# Spark.net
KiCad netlist of a schematic drawn in EAGLE
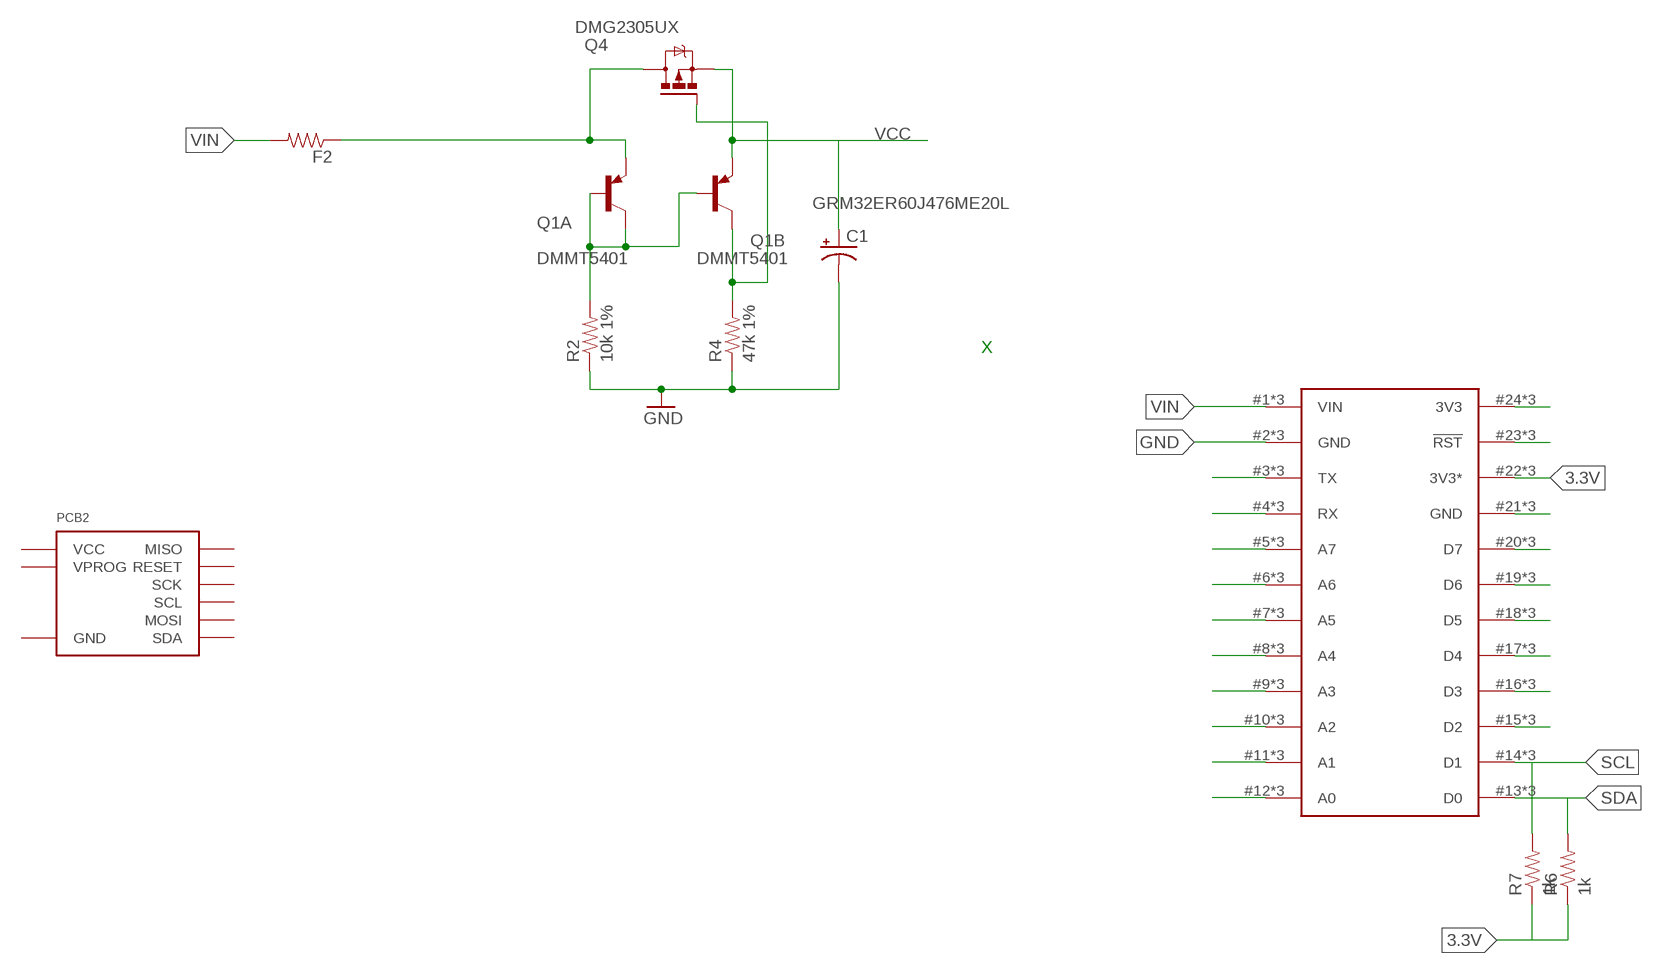
[diagram p0: schematic, sheet 1]

(export (version "E")
  (design (tool "Eeschema 10.0.6"))
  (components
    (comp (ref "C1")
      (value "CAP_POLC")
      (footprint "eagle-import:PANASONIC_C")
      (libsource (lib "eagle-import") (part "CAP_POLC"))
    )
    (comp (ref "F2")
      (value "RESISTOR0805-RES")
      (footprint "eagle-import:0805")
      (libsource (lib "eagle-import") (part "RESISTOR0805-RES"))
    )
    (comp (ref "PCB2")
      (value "EXCLUDE")
      (footprint "eagle-import:DEVICE-PCB")
      (libsource (lib "eagle-import") (part "DEVICE-PCB"))
    )
    (comp (ref "Q1")
      (value "DMMT5401")
      (footprint "eagle-import:SOT-26")
      (libsource (lib "eagle-import") (part "TRANSISTOR-DUAL-PNP"))
    )
    (comp (ref "Q4")
      (value "DMG2305UX")
      (footprint "eagle-import:MICRO3")
      (libsource (lib "eagle-import") (part "IRLML5203"))
    )
    (comp (ref "R2")
      (value "10k 1%")
      (footprint "eagle-import:0805")
      (libsource (lib "eagle-import") (part "RESISTOR0805-RES"))
    )
    (comp (ref "R4")
      (value "47k 1%")
      (footprint "eagle-import:0805")
      (libsource (lib "eagle-import") (part "RESISTOR0805-RES"))
    )
    (comp (ref "R6")
      (value "1k")
      (footprint "eagle-import:0805")
      (libsource (lib "eagle-import") (part "RESISTOR0805-RES"))
    )
    (comp (ref "R7")
      (value "1k")
      (footprint "eagle-import:0805")
      (libsource (lib "eagle-import") (part "RESISTOR0805-RES"))
    )
    (comp (ref "U$1")
      (value "SPARK_CORE")
      (footprint "eagle-import:SPARK_CORE_STACKABLE")
      (libsource (lib "eagle-import") (part "SPARK_CORE"))
    )
  )
  (nets
    (net (code "1") (name "/VCC") (class "Default")
      (node (ref "C1") (pin "+") (pinfunction "+_+") (pintype "passive"))
      (node (ref "Q1") (pin "5") (pinfunction "E_5") (pintype "passive"))
      (node (ref "Q4") (pin "2") (pinfunction "S_2") (pintype "passive"))
    )
    (net (code "2") (name "3.3V") (class "Default")
      (node (ref "R6") (pin "1") (pinfunction "1_1") (pintype "passive"))
      (node (ref "R7") (pin "1") (pinfunction "1_1") (pintype "passive"))
      (node (ref "U$1") (pin "#22") (pinfunction "3V3*_#22") (pintype "power_in"))
      (node (ref "U$1") (pin "22") (pinfunction "3V3*_22") (pintype "power_in"))
      (node (ref "U$1") (pin "@22") (pinfunction "3V3*_@22") (pintype "power_in"))
    )
    (net (code "3") (name "GND") (class "Default")
      (node (ref "C1") (pin "-") (pinfunction "-_-") (pintype "passive"))
      (node (ref "R2") (pin "1") (pinfunction "1_1") (pintype "passive"))
      (node (ref "R4") (pin "1") (pinfunction "1_1") (pintype "passive"))
      (node (ref "U$1") (pin "#2") (pinfunction "GND_#2") (pintype "power_in"))
      (node (ref "U$1") (pin "2") (pinfunction "GND_2") (pintype "power_in"))
      (node (ref "U$1") (pin "@2") (pinfunction "GND_@2") (pintype "power_in"))
    )
    (net (code "4") (name "Net-(Q1A-B)") (class "Default")
      (node (ref "Q1") (pin "1") (pinfunction "C_1") (pintype "passive"))
      (node (ref "Q1") (pin "2") (pinfunction "B_2") (pintype "passive"))
      (node (ref "Q1") (pin "3") (pinfunction "B_3") (pintype "passive"))
      (node (ref "R2") (pin "2") (pinfunction "2_2") (pintype "passive"))
    )
    (net (code "5") (name "Net-(Q1A-E)") (class "Default")
      (node (ref "F2") (pin "1") (pinfunction "1_1") (pintype "passive"))
      (node (ref "Q1") (pin "6") (pinfunction "E_6") (pintype "passive"))
      (node (ref "Q4") (pin "3") (pinfunction "D_3") (pintype "passive"))
    )
    (net (code "6") (name "Net-(Q1B-C)") (class "Default")
      (node (ref "Q1") (pin "4") (pinfunction "C_4") (pintype "passive"))
      (node (ref "Q4") (pin "1") (pinfunction "G_1") (pintype "passive"))
      (node (ref "R4") (pin "2") (pinfunction "2_2") (pintype "passive"))
    )
    (net (code "7") (name "Net-(U$1-3V3-Pad#24)") (class "Default")
      (node (ref "U$1") (pin "#24") (pinfunction "3V3_#24") (pintype "power_in"))
      (node (ref "U$1") (pin "24") (pinfunction "3V3_24") (pintype "power_in"))
      (node (ref "U$1") (pin "@24") (pinfunction "3V3_@24") (pintype "power_in"))
    )
    (net (code "8") (name "Net-(U$1-A0-Pad#12)") (class "Default")
      (node (ref "U$1") (pin "#12") (pinfunction "A0_#12") (pintype "bidirectional"))
      (node (ref "U$1") (pin "12") (pinfunction "A0_12") (pintype "bidirectional"))
      (node (ref "U$1") (pin "@12") (pinfunction "A0_@12") (pintype "bidirectional"))
    )
    (net (code "9") (name "Net-(U$1-A1-Pad#11)") (class "Default")
      (node (ref "U$1") (pin "#11") (pinfunction "A1_#11") (pintype "bidirectional"))
      (node (ref "U$1") (pin "11") (pinfunction "A1_11") (pintype "bidirectional"))
      (node (ref "U$1") (pin "@11") (pinfunction "A1_@11") (pintype "bidirectional"))
    )
    (net (code "10") (name "Net-(U$1-A2-Pad#10)") (class "Default")
      (node (ref "U$1") (pin "#10") (pinfunction "A2_#10") (pintype "bidirectional"))
      (node (ref "U$1") (pin "10") (pinfunction "A2_10") (pintype "bidirectional"))
      (node (ref "U$1") (pin "@10") (pinfunction "A2_@10") (pintype "bidirectional"))
    )
    (net (code "11") (name "Net-(U$1-A3-Pad#9)") (class "Default")
      (node (ref "U$1") (pin "#9") (pinfunction "A3_#9") (pintype "bidirectional"))
      (node (ref "U$1") (pin "9") (pinfunction "A3_9") (pintype "bidirectional"))
      (node (ref "U$1") (pin "@9") (pinfunction "A3_@9") (pintype "bidirectional"))
    )
    (net (code "12") (name "Net-(U$1-A4-Pad#8)") (class "Default")
      (node (ref "U$1") (pin "#8") (pinfunction "A4_#8") (pintype "bidirectional"))
      (node (ref "U$1") (pin "8") (pinfunction "A4_8") (pintype "bidirectional"))
      (node (ref "U$1") (pin "@8") (pinfunction "A4_@8") (pintype "bidirectional"))
    )
    (net (code "13") (name "Net-(U$1-A5-Pad#7)") (class "Default")
      (node (ref "U$1") (pin "#7") (pinfunction "A5_#7") (pintype "bidirectional"))
      (node (ref "U$1") (pin "7") (pinfunction "A5_7") (pintype "bidirectional"))
      (node (ref "U$1") (pin "@7") (pinfunction "A5_@7") (pintype "bidirectional"))
    )
    (net (code "14") (name "Net-(U$1-A6-Pad#6)") (class "Default")
      (node (ref "U$1") (pin "#6") (pinfunction "A6_#6") (pintype "bidirectional"))
      (node (ref "U$1") (pin "6") (pinfunction "A6_6") (pintype "bidirectional"))
      (node (ref "U$1") (pin "@6") (pinfunction "A6_@6") (pintype "bidirectional"))
    )
    (net (code "15") (name "Net-(U$1-A7-Pad#5)") (class "Default")
      (node (ref "U$1") (pin "#5") (pinfunction "A7_#5") (pintype "bidirectional"))
      (node (ref "U$1") (pin "5") (pinfunction "A7_5") (pintype "bidirectional"))
      (node (ref "U$1") (pin "@5") (pinfunction "A7_@5") (pintype "bidirectional"))
    )
    (net (code "16") (name "Net-(U$1-D2-Pad#15)") (class "Default")
      (node (ref "U$1") (pin "#15") (pinfunction "D2_#15") (pintype "bidirectional"))
      (node (ref "U$1") (pin "15") (pinfunction "D2_15") (pintype "bidirectional"))
      (node (ref "U$1") (pin "@15") (pinfunction "D2_@15") (pintype "bidirectional"))
    )
    (net (code "17") (name "Net-(U$1-D3-Pad#16)") (class "Default")
      (node (ref "U$1") (pin "#16") (pinfunction "D3_#16") (pintype "bidirectional"))
      (node (ref "U$1") (pin "16") (pinfunction "D3_16") (pintype "bidirectional"))
      (node (ref "U$1") (pin "@16") (pinfunction "D3_@16") (pintype "bidirectional"))
    )
    (net (code "18") (name "Net-(U$1-D4-Pad#17)") (class "Default")
      (node (ref "U$1") (pin "#17") (pinfunction "D4_#17") (pintype "bidirectional"))
      (node (ref "U$1") (pin "17") (pinfunction "D4_17") (pintype "bidirectional"))
      (node (ref "U$1") (pin "@17") (pinfunction "D4_@17") (pintype "bidirectional"))
    )
    (net (code "19") (name "Net-(U$1-D5-Pad#18)") (class "Default")
      (node (ref "U$1") (pin "#18") (pinfunction "D5_#18") (pintype "bidirectional"))
      (node (ref "U$1") (pin "18") (pinfunction "D5_18") (pintype "bidirectional"))
      (node (ref "U$1") (pin "@18") (pinfunction "D5_@18") (pintype "bidirectional"))
    )
    (net (code "20") (name "Net-(U$1-D6-Pad#19)") (class "Default")
      (node (ref "U$1") (pin "#19") (pinfunction "D6_#19") (pintype "bidirectional"))
      (node (ref "U$1") (pin "19") (pinfunction "D6_19") (pintype "bidirectional"))
      (node (ref "U$1") (pin "@19") (pinfunction "D6_@19") (pintype "bidirectional"))
    )
    (net (code "21") (name "Net-(U$1-D7-Pad#20)") (class "Default")
      (node (ref "U$1") (pin "#20") (pinfunction "D7_#20") (pintype "bidirectional"))
      (node (ref "U$1") (pin "20") (pinfunction "D7_20") (pintype "bidirectional"))
      (node (ref "U$1") (pin "@20") (pinfunction "D7_@20") (pintype "bidirectional"))
    )
    (net (code "22") (name "Net-(U$1-GND-Pad#21)") (class "Default")
      (node (ref "U$1") (pin "#21") (pinfunction "GND_#21") (pintype "power_in"))
      (node (ref "U$1") (pin "21") (pinfunction "GND_21") (pintype "power_in"))
      (node (ref "U$1") (pin "@21") (pinfunction "GND_@21") (pintype "power_in"))
    )
    (net (code "23") (name "Net-(U$1-RX-Pad#4)") (class "Default")
      (node (ref "U$1") (pin "#4") (pinfunction "RX_#4") (pintype "bidirectional"))
      (node (ref "U$1") (pin "4") (pinfunction "RX_4") (pintype "bidirectional"))
      (node (ref "U$1") (pin "@4") (pinfunction "RX_@4") (pintype "bidirectional"))
    )
    (net (code "24") (name "Net-(U$1-TX-Pad#3)") (class "Default")
      (node (ref "U$1") (pin "#3") (pinfunction "TX_#3") (pintype "bidirectional"))
      (node (ref "U$1") (pin "3") (pinfunction "TX_3") (pintype "bidirectional"))
      (node (ref "U$1") (pin "@3") (pinfunction "TX_@3") (pintype "bidirectional"))
    )
    (net (code "25") (name "Net-(U$1-~{RST}-Pad#23)") (class "Default")
      (node (ref "U$1") (pin "#23") (pinfunction "~{RST}_#23") (pintype "bidirectional"))
      (node (ref "U$1") (pin "23") (pinfunction "~{RST}_23") (pintype "bidirectional"))
      (node (ref "U$1") (pin "@23") (pinfunction "~{RST}_@23") (pintype "bidirectional"))
    )
    (net (code "26") (name "SCL") (class "Default")
      (node (ref "R7") (pin "2") (pinfunction "2_2") (pintype "passive"))
      (node (ref "U$1") (pin "#14") (pinfunction "D1_#14") (pintype "bidirectional"))
      (node (ref "U$1") (pin "14") (pinfunction "D1_14") (pintype "bidirectional"))
      (node (ref "U$1") (pin "@14") (pinfunction "D1_@14") (pintype "bidirectional"))
    )
    (net (code "27") (name "SDA") (class "Default")
      (node (ref "R6") (pin "2") (pinfunction "2_2") (pintype "passive"))
      (node (ref "U$1") (pin "#13") (pinfunction "D0_#13") (pintype "bidirectional"))
      (node (ref "U$1") (pin "13") (pinfunction "D0_13") (pintype "bidirectional"))
      (node (ref "U$1") (pin "@13") (pinfunction "D0_@13") (pintype "bidirectional"))
    )
    (net (code "28") (name "VIN") (class "Default")
      (node (ref "F2") (pin "2") (pinfunction "2_2") (pintype "passive"))
      (node (ref "U$1") (pin "#1") (pinfunction "VIN_#1") (pintype "power_in"))
      (node (ref "U$1") (pin "1") (pinfunction "VIN_1") (pintype "power_in"))
      (node (ref "U$1") (pin "@1") (pinfunction "VIN_@1") (pintype "power_in"))
    )
    (net (code "29") (name "unconnected-(PCB2-GND-PadBUS0)") (class "Default")
      (node (ref "PCB2") (pin "BUS0") (pinfunction "GND_BUS0") (pintype "bidirectional"))
    )
    (net (code "30") (name "unconnected-(PCB2-MISO-PadPROG3)") (class "Default")
      (node (ref "PCB2") (pin "PROG3") (pinfunction "MISO_PROG3") (pintype "bidirectional"))
    )
    (net (code "31") (name "unconnected-(PCB2-MOSI-PadPROG4)") (class "Default")
      (node (ref "PCB2") (pin "PROG4") (pinfunction "MOSI_PROG4") (pintype "bidirectional"))
    )
    (net (code "32") (name "unconnected-(PCB2-RESET-PadPROG1)") (class "Default")
      (node (ref "PCB2") (pin "PROG1") (pinfunction "RESET_PROG1") (pintype "bidirectional"))
    )
    (net (code "33") (name "unconnected-(PCB2-SCK-PadPROG2)") (class "Default")
      (node (ref "PCB2") (pin "PROG2") (pinfunction "SCK_PROG2") (pintype "bidirectional"))
    )
    (net (code "34") (name "unconnected-(PCB2-SCL-PadBUS3)") (class "Default")
      (node (ref "PCB2") (pin "BUS3") (pinfunction "SCL_BUS3") (pintype "bidirectional"))
    )
    (net (code "35") (name "unconnected-(PCB2-SDA-PadBUS1)") (class "Default")
      (node (ref "PCB2") (pin "BUS1") (pinfunction "SDA_BUS1") (pintype "bidirectional"))
    )
    (net (code "36") (name "unconnected-(PCB2-VCC-PadBUS2)") (class "Default")
      (node (ref "PCB2") (pin "BUS2") (pinfunction "VCC_BUS2") (pintype "bidirectional"))
    )
    (net (code "37") (name "unconnected-(PCB2-VPROG-PadPROG0)") (class "Default")
      (node (ref "PCB2") (pin "PROG0") (pinfunction "VPROG_PROG0") (pintype "bidirectional"))
    )
  )
)
